# Ethernet_Board.net
KiCad netlist of a schematic drawn in EAGLE
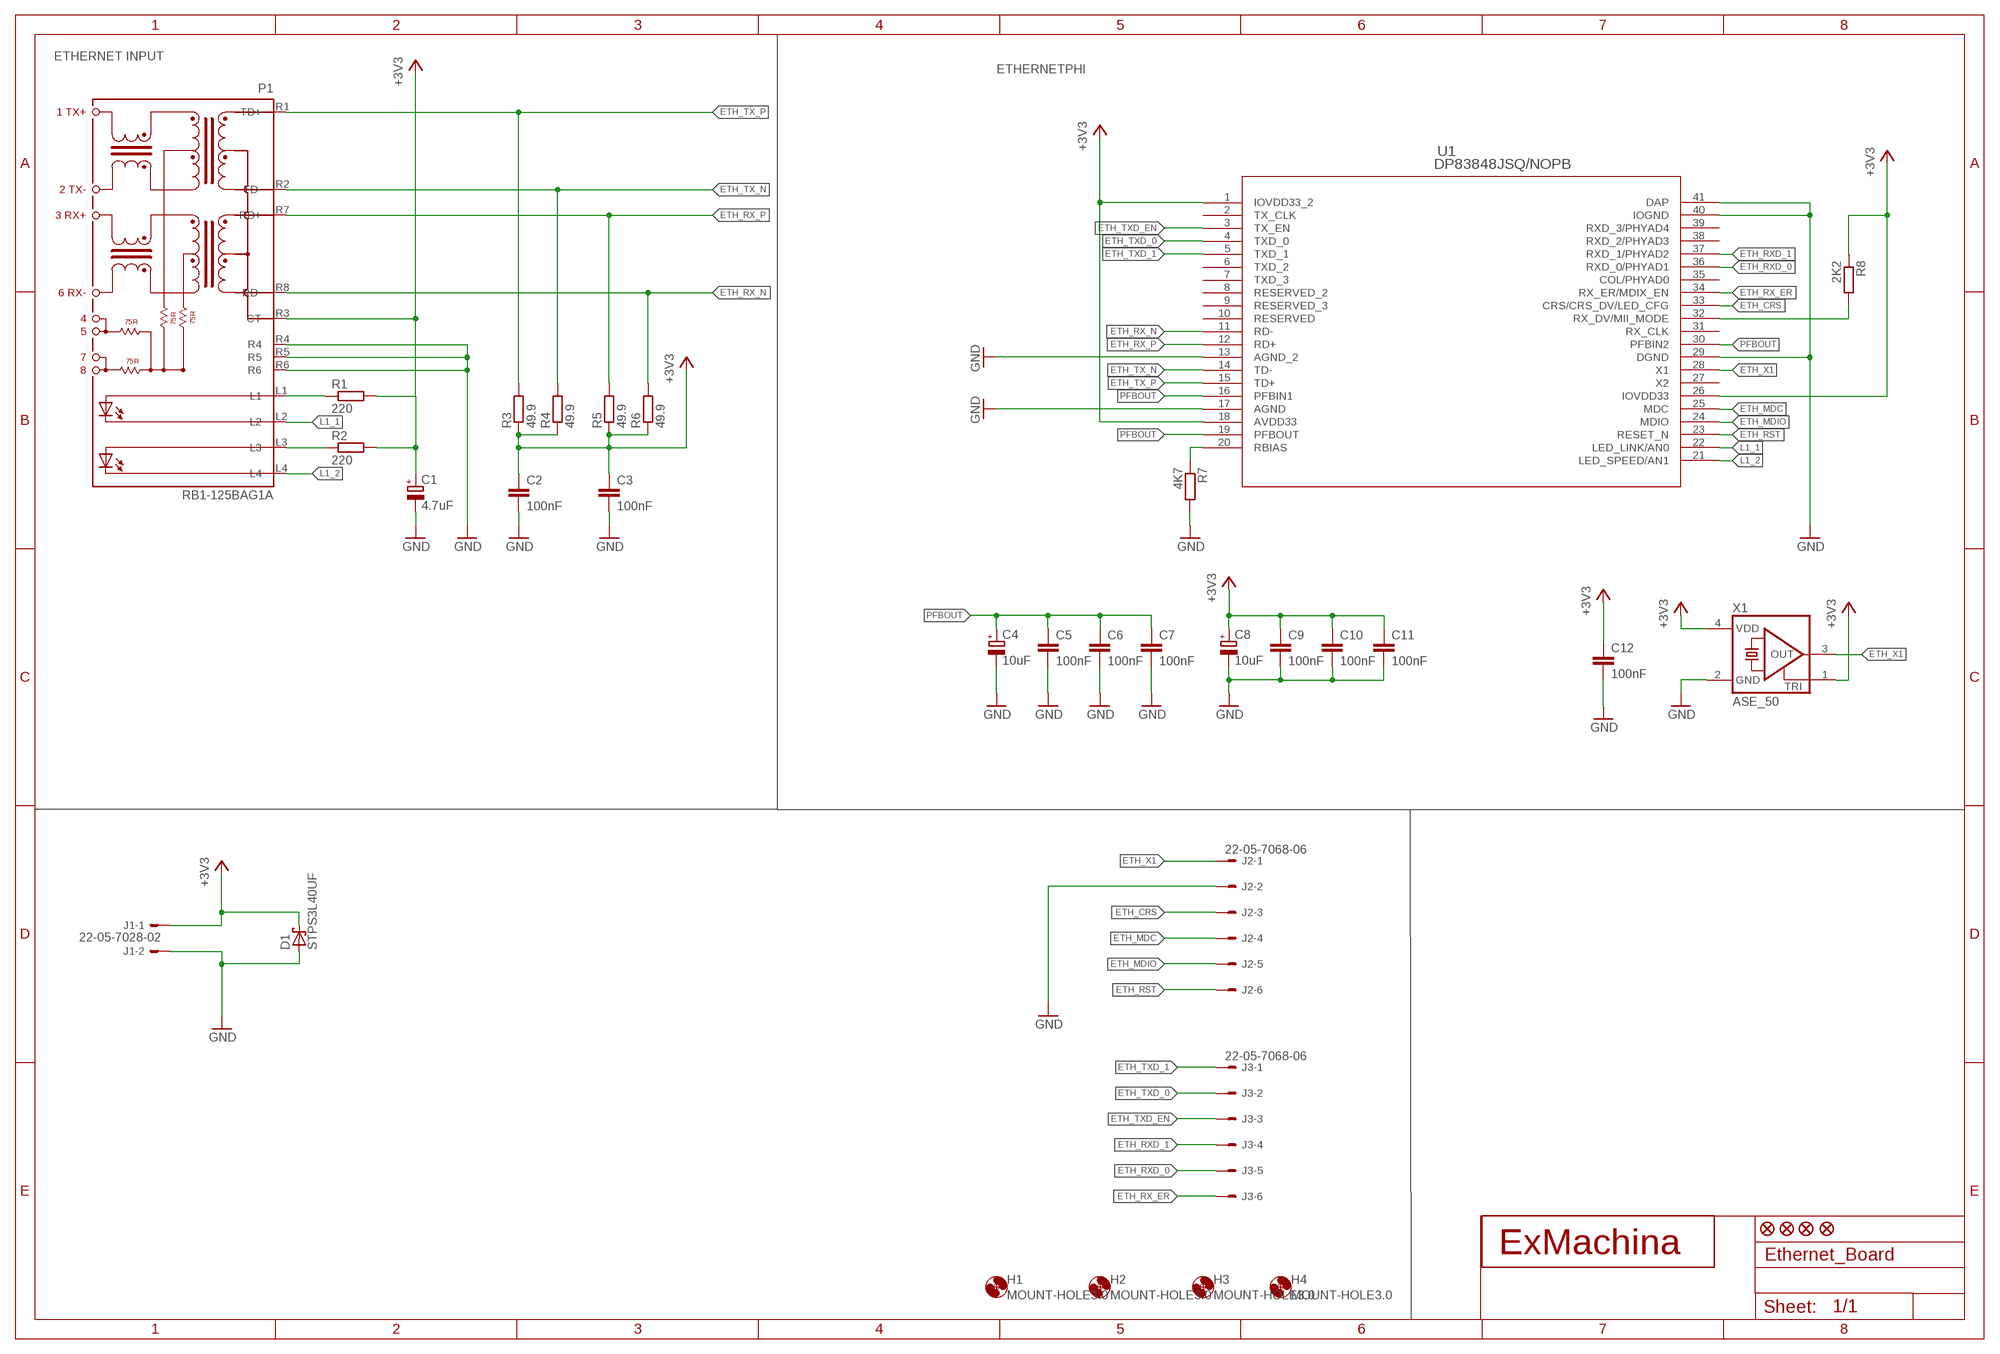
[diagram p0: schematic, sheet 1]

(export (version "E")
  (design (tool "Eeschema 10.0.6"))
  (components
    (comp (ref "C1")
      (value "4.7uF")
      (footprint "eagle-import:CT3216")
      (fields (field (name "MPN") "F931A475MAA"))
      (libsource (lib "eagle-import") (part "CPOL-EUCT3216"))
    )
    (comp (ref "C2")
      (value "100nF")
      (footprint "eagle-import:C0603")
      (fields (field (name "MPN") "MC0603B104K250CT"))
      (libsource (lib "eagle-import") (part "C-EUC0603"))
    )
    (comp (ref "C3")
      (value "100nF")
      (footprint "eagle-import:C0603")
      (fields (field (name "MPN") "MC0603B104K250CT"))
      (libsource (lib "eagle-import") (part "C-EUC0603"))
    )
    (comp (ref "C4")
      (value "10uF")
      (footprint "eagle-import:CT3216")
      (fields (field (name "MPN") "F931A106MAA"))
      (libsource (lib "eagle-import") (part "CPOL-EUCT3216"))
    )
    (comp (ref "C5")
      (value "100nF")
      (footprint "eagle-import:C0603")
      (fields (field (name "MPN") "MC0603B104K250CT"))
      (libsource (lib "eagle-import") (part "C-EUC0603"))
    )
    (comp (ref "C6")
      (value "100nF")
      (footprint "eagle-import:C0603")
      (fields (field (name "MPN") "MC0603B104K250CT"))
      (libsource (lib "eagle-import") (part "C-EUC0603"))
    )
    (comp (ref "C7")
      (value "100nF")
      (footprint "eagle-import:C0603")
      (fields (field (name "MPN") "MC0603B104K250CT"))
      (libsource (lib "eagle-import") (part "C-EUC0603"))
    )
    (comp (ref "C8")
      (value "10uF")
      (footprint "eagle-import:CT3216")
      (fields (field (name "MPN") "F931A106MAA"))
      (libsource (lib "eagle-import") (part "CPOL-EUCT3216"))
    )
    (comp (ref "C9")
      (value "100nF")
      (footprint "eagle-import:C0603")
      (fields (field (name "MPN") "MC0603B104K250CT"))
      (libsource (lib "eagle-import") (part "C-EUC0603"))
    )
    (comp (ref "C10")
      (value "100nF")
      (footprint "eagle-import:C0603")
      (fields (field (name "MPN") "MC0603B104K250CT"))
      (libsource (lib "eagle-import") (part "C-EUC0603"))
    )
    (comp (ref "C11")
      (value "100nF")
      (footprint "eagle-import:C0603")
      (fields (field (name "MPN") "MC0603B104K250CT"))
      (libsource (lib "eagle-import") (part "C-EUC0603"))
    )
    (comp (ref "C12")
      (value "100nF")
      (footprint "eagle-import:C0603")
      (fields (field (name "MPN") "MC0603B104K250CT"))
      (libsource (lib "eagle-import") (part "C-EUC0603"))
    )
    (comp (ref "D1")
      (value "STPS3L40UF")
      (footprint "eagle-import:SMB")
      (fields (field (name "MP") "STMICROELECTRONICS"))
      (libsource (lib "eagle-import") (part "STPS3L40?UF"))
    )
    (comp (ref "H1")
      (value "MOUNT-HOLE3.0")
      (footprint "eagle-import:3,0")
      (libsource (lib "eagle-import") (part "MOUNT-HOLE3.0"))
    )
    (comp (ref "H2")
      (value "MOUNT-HOLE3.0")
      (footprint "eagle-import:3,0")
      (libsource (lib "eagle-import") (part "MOUNT-HOLE3.0"))
    )
    (comp (ref "H3")
      (value "MOUNT-HOLE3.0")
      (footprint "eagle-import:3,0")
      (libsource (lib "eagle-import") (part "MOUNT-HOLE3.0"))
    )
    (comp (ref "H4")
      (value "MOUNT-HOLE3.0")
      (footprint "eagle-import:3,0")
      (libsource (lib "eagle-import") (part "MOUNT-HOLE3.0"))
    )
    (comp (ref "J1")
      (value "22-05-7028-02")
      (footprint "eagle-import:7395-02")
      (fields (field (name "MPN") "22-05-7028") (field (name "OC_NEWARK") "25M1728"))
      (libsource (lib "eagle-import") (part "22-?-0205-7028"))
    )
    (comp (ref "J2")
      (value "22-05-7068-06")
      (footprint "eagle-import:7395-06")
      (fields (field (name "MPN") "22-05-7068") (field (name "OC_NEWARK") "25M1733"))
      (libsource (lib "eagle-import") (part "22-?-0605-7068"))
    )
    (comp (ref "J3")
      (value "22-05-7068-06")
      (footprint "eagle-import:7395-06")
      (fields (field (name "MPN") "22-05-7068") (field (name "OC_NEWARK") "25M1733"))
      (libsource (lib "eagle-import") (part "22-?-0605-7068"))
    )
    (comp (ref "JP1")
      (value "FIDUCIAL1X2")
      (footprint "eagle-import:FIDUCIAL-1X2")
      (libsource (lib "eagle-import") (part "FIDUCIAL1X2"))
    )
    (comp (ref "JP2")
      (value "FIDUCIAL1X2")
      (footprint "eagle-import:FIDUCIAL-1X2")
      (libsource (lib "eagle-import") (part "FIDUCIAL1X2"))
    )
    (comp (ref "JP3")
      (value "FIDUCIAL1X2")
      (footprint "eagle-import:FIDUCIAL-1X2")
      (libsource (lib "eagle-import") (part "FIDUCIAL1X2"))
    )
    (comp (ref "JP4")
      (value "FIDUCIAL1X2")
      (footprint "eagle-import:FIDUCIAL-1X2")
      (libsource (lib "eagle-import") (part "FIDUCIAL1X2"))
    )
    (comp (ref "P1")
      (value "RB1-125BAG1A")
      (footprint "eagle-import:WIZNET_RB1-125BAG1A")
      (libsource (lib "eagle-import") (part "RB1-125BAG1A"))
    )
    (comp (ref "R1")
      (value "220")
      (footprint "eagle-import:R0603")
      (fields (field (name "MPN") "MCMR06X2200FTL"))
      (libsource (lib "eagle-import") (part "R-EU_R0603"))
    )
    (comp (ref "R2")
      (value "220")
      (footprint "eagle-import:R0603")
      (fields (field (name "MPN") "MCMR06X2200FTL"))
      (libsource (lib "eagle-import") (part "R-EU_R0603"))
    )
    (comp (ref "R3")
      (value "49.9")
      (footprint "eagle-import:R0603")
      (fields (field (name "MPN") "MCMR06X49R9FTL"))
      (libsource (lib "eagle-import") (part "R-EU_R0603"))
    )
    (comp (ref "R4")
      (value "49.9")
      (footprint "eagle-import:R0603")
      (fields (field (name "MPN") "MCMR06X49R9FTL"))
      (libsource (lib "eagle-import") (part "R-EU_R0603"))
    )
    (comp (ref "R5")
      (value "49.9")
      (footprint "eagle-import:R0603")
      (fields (field (name "MPN") "MCMR06X49R9FTL"))
      (libsource (lib "eagle-import") (part "R-EU_R0603"))
    )
    (comp (ref "R6")
      (value "49.9")
      (footprint "eagle-import:R0603")
      (fields (field (name "MPN") "MCMR06X49R9FTL"))
      (libsource (lib "eagle-import") (part "R-EU_R0603"))
    )
    (comp (ref "R7")
      (value "4K7")
      (footprint "eagle-import:R0603")
      (fields (field (name "MPN") "MCMR06X4701FTL"))
      (libsource (lib "eagle-import") (part "R-EU_R0603"))
    )
    (comp (ref "R8")
      (value "2K2")
      (footprint "eagle-import:R0603")
      (fields (field (name "MPN") "MCMR06X2201FTL"))
      (libsource (lib "eagle-import") (part "R-EU_R0603"))
    )
    (comp (ref "T1")
      (value "EXMACHINA-LOGO-NAME")
      (footprint "eagle-import:EXM-LOGO-BASELINE")
      (libsource (lib "eagle-import") (part "EXMACHINA-LOGO-NAME"))
    )
    (comp (ref "U1")
      (value "DP83848JSQ/NOPB")
      (footprint "eagle-import:SQA40B")
      (fields
        (field (name "MANUFACTURER_PART_NUMBER") "dp83848jsqnopb")
        (field (name "COPYRIGHT") "Copyright C 2015 Accelerated Designs. All rights reserved")
      )
      (libsource (lib "eagle-import") (part "DP83848JSQ/NOPB"))
    )
    (comp (ref "X1")
      (value "ASE_50")
      (footprint "eagle-import:ASE")
      (fields (field (name "MPN") "ASE-50.000MHZ-LC-T") (field (name "OC_NEWARK") "84R2105"))
      (libsource (lib "eagle-import") (part "ASE"))
    )
  )
  (nets
    (net (code "1") (name "+3V3") (class "Default")
      (node (ref "C1") (pin "+") (pinfunction "+_+") (pintype "passive"))
      (node (ref "C10") (pin "1") (pinfunction "1_1") (pintype "passive"))
      (node (ref "C11") (pin "1") (pinfunction "1_1") (pintype "passive"))
      (node (ref "C12") (pin "1") (pinfunction "1_1") (pintype "passive"))
      (node (ref "C2") (pin "1") (pinfunction "1_1") (pintype "passive"))
      (node (ref "C3") (pin "1") (pinfunction "1_1") (pintype "passive"))
      (node (ref "C8") (pin "+") (pinfunction "+_+") (pintype "passive"))
      (node (ref "C9") (pin "1") (pinfunction "1_1") (pintype "passive"))
      (node (ref "D1") (pin "C") (pinfunction "C_C") (pintype "passive"))
      (node (ref "J1") (pin "1") (pinfunction "S_1") (pintype "passive"))
      (node (ref "P1") (pin "R3") (pinfunction "CT_R3") (pintype "input"))
      (node (ref "R1") (pin "2") (pinfunction "2_2") (pintype "passive"))
      (node (ref "R2") (pin "2") (pinfunction "2_2") (pintype "passive"))
      (node (ref "R3") (pin "1") (pinfunction "1_1") (pintype "passive"))
      (node (ref "R4") (pin "1") (pinfunction "1_1") (pintype "passive"))
      (node (ref "R5") (pin "1") (pinfunction "1_1") (pintype "passive"))
      (node (ref "R6") (pin "1") (pinfunction "1_1") (pintype "passive"))
      (node (ref "R8") (pin "1") (pinfunction "1_1") (pintype "passive"))
      (node (ref "U1") (pin "1") (pinfunction "IOVDD33_2_1") (pintype "power_in"))
      (node (ref "U1") (pin "18") (pinfunction "AVDD33_18") (pintype "power_in"))
      (node (ref "U1") (pin "26") (pinfunction "IOVDD33_26") (pintype "power_in"))
      (node (ref "X1") (pin "1") (pinfunction "TRI_1") (pintype "input"))
      (node (ref "X1") (pin "4") (pinfunction "VDD_4") (pintype "power_in"))
    )
    (net (code "2") (name "ETH_CRS") (class "Default")
      (node (ref "J2") (pin "3") (pinfunction "S_3") (pintype "passive"))
      (node (ref "U1") (pin "33") (pinfunction "CRS/CRS_DV/LED_CFG_33") (pintype "output"))
    )
    (net (code "3") (name "ETH_MDC") (class "Default")
      (node (ref "J2") (pin "4") (pinfunction "S_4") (pintype "passive"))
      (node (ref "U1") (pin "25") (pinfunction "MDC_25") (pintype "input"))
    )
    (net (code "4") (name "ETH_MDIO") (class "Default")
      (node (ref "J2") (pin "5") (pinfunction "S_5") (pintype "passive"))
      (node (ref "U1") (pin "24") (pinfunction "MDIO_24") (pintype "bidirectional"))
    )
    (net (code "5") (name "ETH_RST") (class "Default")
      (node (ref "J2") (pin "6") (pinfunction "S_6") (pintype "passive"))
      (node (ref "U1") (pin "23") (pinfunction "RESET_N_23") (pintype "input"))
    )
    (net (code "6") (name "ETH_RXD_0") (class "Default")
      (node (ref "J3") (pin "5") (pinfunction "S_5") (pintype "passive"))
      (node (ref "U1") (pin "36") (pinfunction "RXD_0/PHYAD1_36") (pintype "output"))
    )
    (net (code "7") (name "ETH_RXD_1") (class "Default")
      (node (ref "J3") (pin "4") (pinfunction "S_4") (pintype "passive"))
      (node (ref "U1") (pin "37") (pinfunction "RXD_1/PHYAD2_37") (pintype "output"))
    )
    (net (code "8") (name "ETH_RX_ER") (class "Default")
      (node (ref "J3") (pin "6") (pinfunction "S_6") (pintype "passive"))
      (node (ref "U1") (pin "34") (pinfunction "RX_ER/MDIX_EN_34") (pintype "output"))
    )
    (net (code "9") (name "ETH_RX_N") (class "Default")
      (node (ref "P1") (pin "R8") (pinfunction "RD-_R8") (pintype "input"))
      (node (ref "R6") (pin "2") (pinfunction "2_2") (pintype "passive"))
      (node (ref "U1") (pin "11") (pinfunction "RD-_11") (pintype "bidirectional"))
    )
    (net (code "10") (name "ETH_RX_P") (class "Default")
      (node (ref "P1") (pin "R7") (pinfunction "RD+_R7") (pintype "input"))
      (node (ref "R5") (pin "2") (pinfunction "2_2") (pintype "passive"))
      (node (ref "U1") (pin "12") (pinfunction "RD+_12") (pintype "bidirectional"))
    )
    (net (code "11") (name "ETH_TXD_0") (class "Default")
      (node (ref "J3") (pin "2") (pinfunction "S_2") (pintype "passive"))
      (node (ref "U1") (pin "4") (pinfunction "TXD_0_4") (pintype "input"))
    )
    (net (code "12") (name "ETH_TXD_1") (class "Default")
      (node (ref "J3") (pin "1") (pinfunction "S_1") (pintype "passive"))
      (node (ref "U1") (pin "5") (pinfunction "TXD_1_5") (pintype "input"))
    )
    (net (code "13") (name "ETH_TXD_EN") (class "Default")
      (node (ref "J3") (pin "3") (pinfunction "S_3") (pintype "passive"))
      (node (ref "U1") (pin "3") (pinfunction "TX_EN_3") (pintype "input"))
    )
    (net (code "14") (name "ETH_TX_N") (class "Default")
      (node (ref "P1") (pin "R2") (pinfunction "TD-_R2") (pintype "input"))
      (node (ref "R4") (pin "2") (pinfunction "2_2") (pintype "passive"))
      (node (ref "U1") (pin "14") (pinfunction "TD-_14") (pintype "bidirectional"))
    )
    (net (code "15") (name "ETH_TX_P") (class "Default")
      (node (ref "P1") (pin "R1") (pinfunction "TD+_R1") (pintype "input"))
      (node (ref "R3") (pin "2") (pinfunction "2_2") (pintype "passive"))
      (node (ref "U1") (pin "15") (pinfunction "TD+_15") (pintype "bidirectional"))
    )
    (net (code "16") (name "ETH_X1") (class "Default")
      (node (ref "J2") (pin "1") (pinfunction "S_1") (pintype "passive"))
      (node (ref "U1") (pin "28") (pinfunction "X1_28") (pintype "input"))
      (node (ref "X1") (pin "3") (pinfunction "OUT_3") (pintype "output"))
    )
    (net (code "17") (name "GND") (class "Default")
      (node (ref "C1") (pin "-") (pinfunction "-_-") (pintype "passive"))
      (node (ref "C10") (pin "2") (pinfunction "2_2") (pintype "passive"))
      (node (ref "C11") (pin "2") (pinfunction "2_2") (pintype "passive"))
      (node (ref "C12") (pin "2") (pinfunction "2_2") (pintype "passive"))
      (node (ref "C2") (pin "2") (pinfunction "2_2") (pintype "passive"))
      (node (ref "C3") (pin "2") (pinfunction "2_2") (pintype "passive"))
      (node (ref "C4") (pin "-") (pinfunction "-_-") (pintype "passive"))
      (node (ref "C5") (pin "2") (pinfunction "2_2") (pintype "passive"))
      (node (ref "C6") (pin "2") (pinfunction "2_2") (pintype "passive"))
      (node (ref "C7") (pin "2") (pinfunction "2_2") (pintype "passive"))
      (node (ref "C8") (pin "-") (pinfunction "-_-") (pintype "passive"))
      (node (ref "C9") (pin "2") (pinfunction "2_2") (pintype "passive"))
      (node (ref "D1") (pin "A") (pinfunction "A_A") (pintype "passive"))
      (node (ref "J1") (pin "2") (pinfunction "S_2") (pintype "passive"))
      (node (ref "J2") (pin "2") (pinfunction "S_2") (pintype "passive"))
      (node (ref "P1") (pin "R4") (pinfunction "R4_R4") (pintype "input"))
      (node (ref "P1") (pin "R5") (pinfunction "R5_R5") (pintype "input"))
      (node (ref "P1") (pin "R6") (pinfunction "R6_R6") (pintype "input"))
      (node (ref "R7") (pin "2") (pinfunction "2_2") (pintype "passive"))
      (node (ref "U1") (pin "13") (pinfunction "AGND_2_13") (pintype "power_in"))
      (node (ref "U1") (pin "17") (pinfunction "AGND_17") (pintype "power_in"))
      (node (ref "U1") (pin "29") (pinfunction "DGND_29") (pintype "power_in"))
      (node (ref "U1") (pin "40") (pinfunction "IOGND_40") (pintype "power_in"))
      (node (ref "U1") (pin "41") (pinfunction "DAP_41") (pintype "passive"))
      (node (ref "X1") (pin "2") (pinfunction "GND_2") (pintype "power_in"))
    )
    (net (code "18") (name "L1_1") (class "Default")
      (node (ref "P1") (pin "L2") (pinfunction "L2_L2") (pintype "passive"))
      (node (ref "U1") (pin "22") (pinfunction "LED_LINK/AN0_22") (pintype "output"))
    )
    (net (code "19") (name "L1_2") (class "Default")
      (node (ref "P1") (pin "L4") (pinfunction "L4_L4") (pintype "passive"))
      (node (ref "U1") (pin "21") (pinfunction "LED_SPEED/AN1_21") (pintype "output"))
    )
    (net (code "20") (name "Net-(P1-PadL1)") (class "Default")
      (node (ref "P1") (pin "L1") (pinfunction "L1_L1") (pintype "passive"))
      (node (ref "R1") (pin "1") (pinfunction "1_1") (pintype "passive"))
    )
    (net (code "21") (name "Net-(P1-PadL3)") (class "Default")
      (node (ref "P1") (pin "L3") (pinfunction "L3_L3") (pintype "passive"))
      (node (ref "R2") (pin "1") (pinfunction "1_1") (pintype "passive"))
    )
    (net (code "22") (name "Net-(U1-RBIAS)") (class "Default")
      (node (ref "R7") (pin "1") (pinfunction "1_1") (pintype "passive"))
      (node (ref "U1") (pin "20") (pinfunction "RBIAS_20") (pintype "input"))
    )
    (net (code "23") (name "Net-(U1-RX_DV{slash}MII_MODE)") (class "Default")
      (node (ref "R8") (pin "2") (pinfunction "2_2") (pintype "passive"))
      (node (ref "U1") (pin "32") (pinfunction "RX_DV/MII_MODE_32") (pintype "output"))
    )
    (net (code "24") (name "PFBOUT") (class "Default")
      (node (ref "C4") (pin "+") (pinfunction "+_+") (pintype "passive"))
      (node (ref "C5") (pin "1") (pinfunction "1_1") (pintype "passive"))
      (node (ref "C6") (pin "1") (pinfunction "1_1") (pintype "passive"))
      (node (ref "C7") (pin "1") (pinfunction "1_1") (pintype "passive"))
      (node (ref "U1") (pin "16") (pinfunction "PFBIN1_16") (pintype "input"))
      (node (ref "U1") (pin "19") (pinfunction "PFBOUT_19") (pintype "output"))
      (node (ref "U1") (pin "30") (pinfunction "PFBIN2_30") (pintype "input"))
    )
    (net (code "25") (name "unconnected-(U1-COL{slash}PHYAD0-Pad35)") (class "Default")
      (node (ref "U1") (pin "35") (pinfunction "COL/PHYAD0_35") (pintype "output"))
    )
    (net (code "26") (name "unconnected-(U1-RESERVED-Pad10)") (class "Default")
      (node (ref "U1") (pin "10") (pinfunction "RESERVED_10") (pintype "bidirectional"))
    )
    (net (code "27") (name "unconnected-(U1-RESERVED_2-Pad8)") (class "Default")
      (node (ref "U1") (pin "8") (pinfunction "RESERVED_2_8") (pintype "bidirectional"))
    )
    (net (code "28") (name "unconnected-(U1-RESERVED_3-Pad9)") (class "Default")
      (node (ref "U1") (pin "9") (pinfunction "RESERVED_3_9") (pintype "bidirectional"))
    )
    (net (code "29") (name "unconnected-(U1-RXD_2{slash}PHYAD3-Pad38)") (class "Default")
      (node (ref "U1") (pin "38") (pinfunction "RXD_2/PHYAD3_38") (pintype "output"))
    )
    (net (code "30") (name "unconnected-(U1-RXD_3{slash}PHYAD4-Pad39)") (class "Default")
      (node (ref "U1") (pin "39") (pinfunction "RXD_3/PHYAD4_39") (pintype "output"))
    )
    (net (code "31") (name "unconnected-(U1-RX_CLK-Pad31)") (class "Default")
      (node (ref "U1") (pin "31") (pinfunction "RX_CLK_31") (pintype "output"))
    )
    (net (code "32") (name "unconnected-(U1-TXD_2-Pad6)") (class "Default")
      (node (ref "U1") (pin "6") (pinfunction "TXD_2_6") (pintype "input"))
    )
    (net (code "33") (name "unconnected-(U1-TXD_3-Pad7)") (class "Default")
      (node (ref "U1") (pin "7") (pinfunction "TXD_3_7") (pintype "input"))
    )
    (net (code "34") (name "unconnected-(U1-TX_CLK-Pad2)") (class "Default")
      (node (ref "U1") (pin "2") (pinfunction "TX_CLK_2") (pintype "output"))
    )
    (net (code "35") (name "unconnected-(U1-X2-Pad27)") (class "Default")
      (node (ref "U1") (pin "27") (pinfunction "X2_27") (pintype "output"))
    )
  )
)
